# POWER_4.net
KiCad netlist of a schematic drawn in Altium Designer
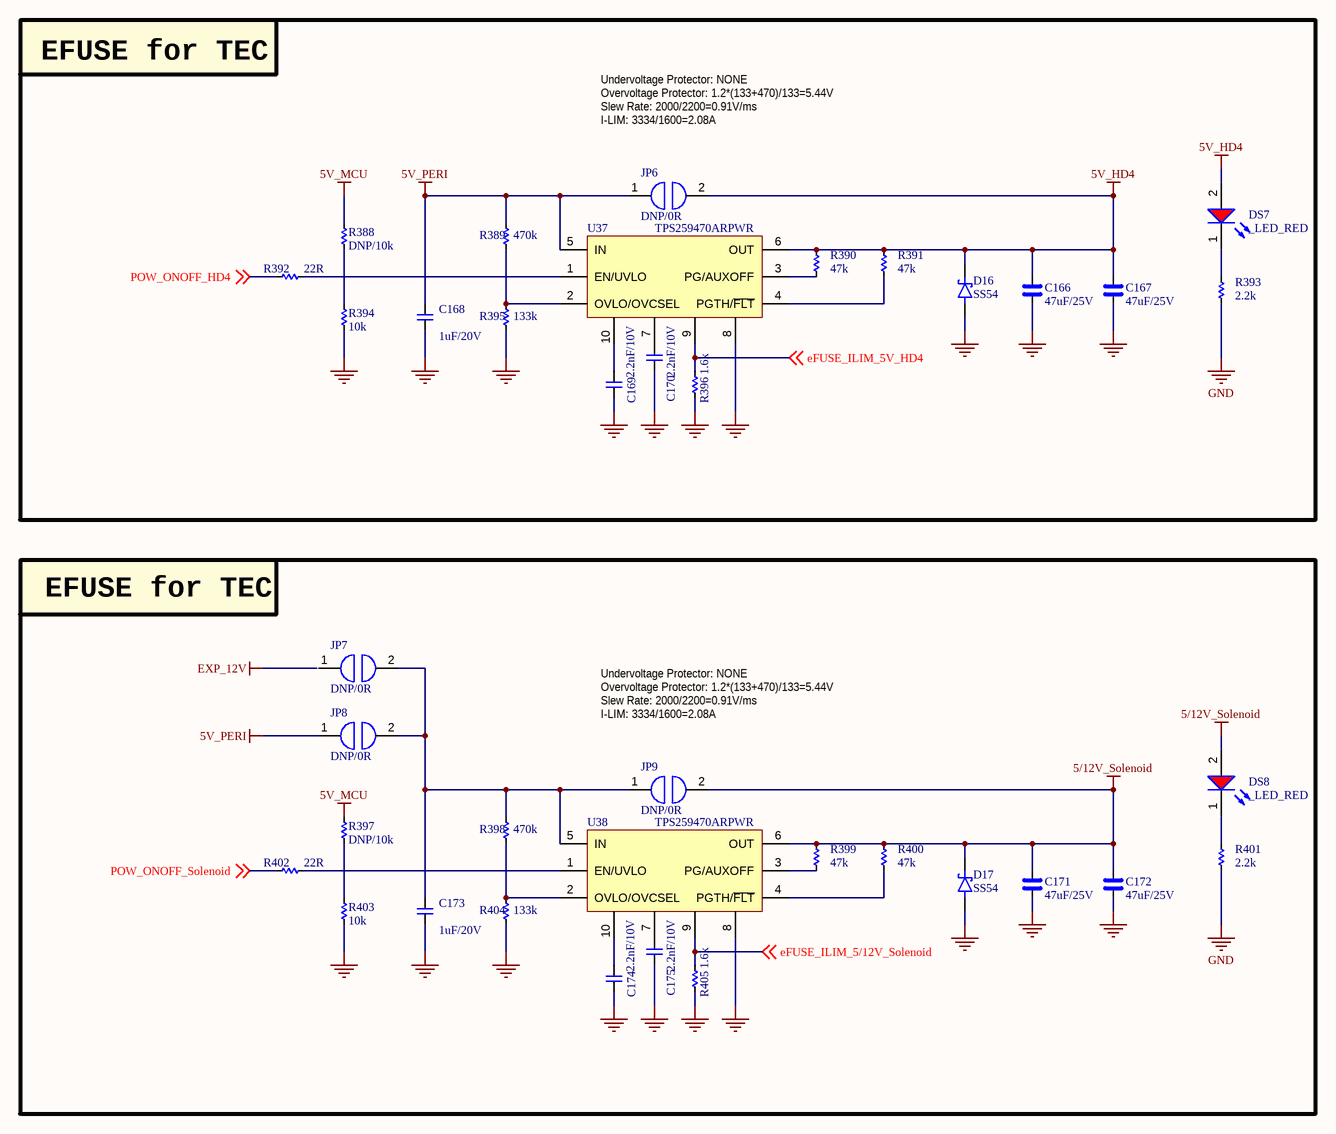
[diagram p0: POWER_4.SchDoc]

(export (version "E")
  (design (tool "Eeschema 10.0.6"))
  (components
    (comp (ref "C166")
      (value "47uF/25V")
      (footprint "CAP_C_3225X80")
      (description "CAP CHIP High Value")
      (libsource (lib "LABLIB") (part "_CAP_C_High_2"))
    )
    (comp (ref "C167")
      (value "47uF/25V")
      (footprint "CAP_C_3225X80")
      (description "CAP CHIP High Value")
      (libsource (lib "LABLIB") (part "_CAP_C_High_2"))
    )
    (comp (ref "C168")
      (value "1uF/20V")
      (footprint "CAP_C_1005X60")
      (description "CAP CHIP")
      (libsource (lib "LABLIB") (part "_CAP_C_2"))
    )
    (comp (ref "C169")
      (value "2.2nF/10V")
      (footprint "CAP_C_1005X60")
      (description "CAP CHIP")
      (libsource (lib "LABLIB") (part "_CAP_C_2"))
    )
    (comp (ref "C170")
      (value "2.2nF/10V")
      (footprint "CAP_C_1005X60")
      (description "CAP CHIP")
      (libsource (lib "LABLIB") (part "_CAP_C_2"))
    )
    (comp (ref "C171")
      (value "47uF/25V")
      (footprint "CAP_C_3225X80")
      (description "CAP CHIP High Value")
      (libsource (lib "LABLIB") (part "_CAP_C_High_2"))
    )
    (comp (ref "C172")
      (value "47uF/25V")
      (footprint "CAP_C_3225X80")
      (description "CAP CHIP High Value")
      (libsource (lib "LABLIB") (part "_CAP_C_High_2"))
    )
    (comp (ref "C173")
      (value "1uF/20V")
      (footprint "CAP_C_1005X60")
      (description "CAP CHIP")
      (libsource (lib "LABLIB") (part "_CAP_C_2"))
    )
    (comp (ref "C174")
      (value "2.2nF/10V")
      (footprint "CAP_C_1005X60")
      (description "CAP CHIP")
      (libsource (lib "LABLIB") (part "_CAP_C_2"))
    )
    (comp (ref "C175")
      (value "2.2nF/10V")
      (footprint "CAP_C_1005X60")
      (description "CAP CHIP")
      (libsource (lib "LABLIB") (part "_CAP_C_2"))
    )
    (comp (ref "D16")
      (value "SS54")
      (footprint "DO-214AC_SMA")
      (description "DIODE SCHOTTKY")
      (libsource (lib "LABLIB") (part "DIODE SCHOTTKY"))
    )
    (comp (ref "D17")
      (value "SS54")
      (footprint "DO-214AC_SMA")
      (description "DIODE SCHOTTKY")
      (libsource (lib "LABLIB") (part "DIODE SCHOTTKY"))
    )
    (comp (ref "DS7") (value "_LED_RED") (footprint "LED_0402") (libsource (lib "LABLIB") (part "_LED_RED")))
    (comp (ref "DS8") (value "_LED_RED") (footprint "LED_0402") (libsource (lib "LABLIB") (part "_LED_RED")))
    (comp (ref "JP6") (value "DNP/0R") (footprint "RES_C_1608X60") (libsource (lib "EXP_V1") (part "JUMPER")))
    (comp (ref "JP7") (value "DNP/0R") (footprint "RES_C_1608X60") (libsource (lib "EXP_V1") (part "JUMPER")))
    (comp (ref "JP8") (value "DNP/0R") (footprint "RES_C_1608X60") (libsource (lib "EXP_V1") (part "JUMPER")))
    (comp (ref "JP9") (value "DNP/0R") (footprint "RES_C_1608X60") (libsource (lib "EXP_V1") (part "JUMPER")))
    (comp (ref "R388")
      (value "DNP/10k")
      (footprint "RES_C_1005X40")
      (description "RES")
      (libsource (lib "LABLIB") (part "_RES_B_2"))
    )
    (comp (ref "R389")
      (value "470k")
      (footprint "RES_C_1005X40")
      (description "RES")
      (libsource (lib "LABLIB") (part "_RES_B_2"))
    )
    (comp (ref "R390")
      (value "47k")
      (footprint "RES_C_1005X40")
      (description "RES")
      (libsource (lib "LABLIB") (part "_RES_B_2"))
    )
    (comp (ref "R391")
      (value "47k")
      (footprint "RES_C_1005X40")
      (description "RES")
      (libsource (lib "LABLIB") (part "_RES_B_2"))
    )
    (comp (ref "R392")
      (value "22R")
      (footprint "RES_C_1005X40")
      (description "RES")
      (libsource (lib "LABLIB") (part "_RES_B_2"))
    )
    (comp (ref "R393")
      (value "2.2k")
      (footprint "RES_C_1005X40")
      (description "RES")
      (libsource (lib "LABLIB") (part "_RES_B_2"))
    )
    (comp (ref "R394")
      (value "10k")
      (footprint "RES_C_1005X40")
      (description "RES")
      (libsource (lib "LABLIB") (part "_RES_B_2"))
    )
    (comp (ref "R395")
      (value "133k")
      (footprint "RES_C_1005X40")
      (description "RES")
      (libsource (lib "LABLIB") (part "_RES_B_2"))
    )
    (comp (ref "R396")
      (value "1.6k")
      (footprint "RES_C_1005X40")
      (description "RES")
      (libsource (lib "LABLIB") (part "_RES_B_2"))
    )
    (comp (ref "R397")
      (value "DNP/10k")
      (footprint "RES_C_1005X40")
      (description "RES")
      (libsource (lib "LABLIB") (part "_RES_B_2"))
    )
    (comp (ref "R398")
      (value "470k")
      (footprint "RES_C_1005X40")
      (description "RES")
      (libsource (lib "LABLIB") (part "_RES_B_2"))
    )
    (comp (ref "R399")
      (value "47k")
      (footprint "RES_C_1005X40")
      (description "RES")
      (libsource (lib "LABLIB") (part "_RES_B_2"))
    )
    (comp (ref "R400")
      (value "47k")
      (footprint "RES_C_1005X40")
      (description "RES")
      (libsource (lib "LABLIB") (part "_RES_B_2"))
    )
    (comp (ref "R401")
      (value "2.2k")
      (footprint "RES_C_1005X40")
      (description "RES")
      (libsource (lib "LABLIB") (part "_RES_B_2"))
    )
    (comp (ref "R402")
      (value "22R")
      (footprint "RES_C_1005X40")
      (description "RES")
      (libsource (lib "LABLIB") (part "_RES_B_2"))
    )
    (comp (ref "R403")
      (value "10k")
      (footprint "RES_C_1005X40")
      (description "RES")
      (libsource (lib "LABLIB") (part "_RES_B_2"))
    )
    (comp (ref "R404")
      (value "133k")
      (footprint "RES_C_1005X40")
      (description "RES")
      (libsource (lib "LABLIB") (part "_RES_B_2"))
    )
    (comp (ref "R405")
      (value "1.6k")
      (footprint "RES_C_1005X40")
      (description "RES")
      (libsource (lib "LABLIB") (part "_RES_B_2"))
    )
    (comp (ref "U37")
      (value "TPS259470ARPWR")
      (footprint "VQFN-HR-10")
      (libsource (lib "EXP_HW_V3") (part "TPS259470ARPWR"))
    )
    (comp (ref "U38")
      (value "TPS259470ARPWR")
      (footprint "VQFN-HR-10")
      (libsource (lib "EXP_HW_V3") (part "TPS259470ARPWR"))
    )
  )
  (nets
    (net (code "1") (name "5V_HD4") (class "Default")
      (node (ref "C166") (pin "2") (pinfunction "2_2") (pintype "passive"))
      (node (ref "C167") (pin "2") (pinfunction "2_2") (pintype "passive"))
      (node (ref "D16") (pin "1") (pinfunction "K_1") (pintype "passive"))
      (node (ref "DS7") (pin "2") (pinfunction "A_2") (pintype "passive"))
      (node (ref "JP6") (pin "2") (pinfunction "2_2") (pintype "passive"))
      (node (ref "R390") (pin "2") (pinfunction "2_2") (pintype "passive"))
      (node (ref "R391") (pin "2") (pinfunction "2_2") (pintype "passive"))
      (node (ref "U37") (pin "6") (pinfunction "OUT_6") (pintype "passive"))
    )
    (net (code "2") (name "5V_MCU") (class "Default")
      (node (ref "R388") (pin "1") (pinfunction "1_1") (pintype "passive"))
      (node (ref "R397") (pin "1") (pinfunction "1_1") (pintype "passive"))
    )
    (net (code "3") (name "5V_PERI") (class "Default")
      (node (ref "C168") (pin "2") (pinfunction "2_2") (pintype "passive"))
      (node (ref "JP6") (pin "1") (pinfunction "1_1") (pintype "passive"))
      (node (ref "JP8") (pin "1") (pinfunction "1_1") (pintype "passive"))
      (node (ref "R389") (pin "2") (pinfunction "2_2") (pintype "passive"))
      (node (ref "U37") (pin "5") (pinfunction "IN_5") (pintype "passive"))
    )
    (net (code "4") (name "5{slash}12V_Solenoid") (class "Default")
      (node (ref "C171") (pin "2") (pinfunction "2_2") (pintype "passive"))
      (node (ref "C172") (pin "2") (pinfunction "2_2") (pintype "passive"))
      (node (ref "D17") (pin "1") (pinfunction "K_1") (pintype "passive"))
      (node (ref "DS8") (pin "2") (pinfunction "A_2") (pintype "passive"))
      (node (ref "JP9") (pin "2") (pinfunction "2_2") (pintype "passive"))
      (node (ref "R399") (pin "2") (pinfunction "2_2") (pintype "passive"))
      (node (ref "R400") (pin "2") (pinfunction "2_2") (pintype "passive"))
      (node (ref "U38") (pin "6") (pinfunction "OUT_6") (pintype "passive"))
    )
    (net (code "6") (name "GND") (class "Default")
      (node (ref "C166") (pin "1") (pinfunction "1_1") (pintype "passive"))
      (node (ref "C167") (pin "1") (pinfunction "1_1") (pintype "passive"))
      (node (ref "C168") (pin "1") (pinfunction "1_1") (pintype "passive"))
      (node (ref "C169") (pin "1") (pinfunction "1_1") (pintype "passive"))
      (node (ref "C170") (pin "1") (pinfunction "1_1") (pintype "passive"))
      (node (ref "C171") (pin "1") (pinfunction "1_1") (pintype "passive"))
      (node (ref "C172") (pin "1") (pinfunction "1_1") (pintype "passive"))
      (node (ref "C173") (pin "1") (pinfunction "1_1") (pintype "passive"))
      (node (ref "C174") (pin "1") (pinfunction "1_1") (pintype "passive"))
      (node (ref "C175") (pin "1") (pinfunction "1_1") (pintype "passive"))
      (node (ref "D16") (pin "2") (pinfunction "A_2") (pintype "passive"))
      (node (ref "D17") (pin "2") (pinfunction "A_2") (pintype "passive"))
      (node (ref "R393") (pin "1") (pinfunction "1_1") (pintype "passive"))
      (node (ref "R394") (pin "2") (pinfunction "2_2") (pintype "passive"))
      (node (ref "R395") (pin "1") (pinfunction "1_1") (pintype "passive"))
      (node (ref "R396") (pin "1") (pinfunction "1_1") (pintype "passive"))
      (node (ref "R401") (pin "1") (pinfunction "1_1") (pintype "passive"))
      (node (ref "R403") (pin "2") (pinfunction "2_2") (pintype "passive"))
      (node (ref "R404") (pin "1") (pinfunction "1_1") (pintype "passive"))
      (node (ref "R405") (pin "1") (pinfunction "1_1") (pintype "passive"))
      (node (ref "U37") (pin "8") (pinfunction "8_8") (pintype "passive"))
      (node (ref "U38") (pin "8") (pinfunction "8_8") (pintype "passive"))
    )
    (net (code "7") (name "Net-(C169-Pad2)") (class "Default")
      (node (ref "C169") (pin "2") (pinfunction "2_2") (pintype "passive"))
      (node (ref "U37") (pin "10") (pinfunction "10_10") (pintype "passive"))
    )
    (net (code "8") (name "Net-(C170-Pad2)") (class "Default")
      (node (ref "C170") (pin "2") (pinfunction "2_2") (pintype "passive"))
      (node (ref "U37") (pin "7") (pinfunction "7_7") (pintype "passive"))
    )
    (net (code "9") (name "Net-(C174-Pad2)") (class "Default")
      (node (ref "C174") (pin "2") (pinfunction "2_2") (pintype "passive"))
      (node (ref "U38") (pin "10") (pinfunction "10_10") (pintype "passive"))
    )
    (net (code "10") (name "Net-(C175-Pad2)") (class "Default")
      (node (ref "C175") (pin "2") (pinfunction "2_2") (pintype "passive"))
      (node (ref "U38") (pin "7") (pinfunction "7_7") (pintype "passive"))
    )
    (net (code "11") (name "Net-(DS7-K)") (class "Default")
      (node (ref "DS7") (pin "1") (pinfunction "K_1") (pintype "passive"))
      (node (ref "R393") (pin "2") (pinfunction "2_2") (pintype "passive"))
    )
    (net (code "12") (name "Net-(DS8-K)") (class "Default")
      (node (ref "DS8") (pin "1") (pinfunction "K_1") (pintype "passive"))
      (node (ref "R401") (pin "2") (pinfunction "2_2") (pintype "passive"))
    )
    (net (code "13") (name "Net-(R388-Pad2)") (class "Default")
      (node (ref "R388") (pin "2") (pinfunction "2_2") (pintype "passive"))
      (node (ref "R394") (pin "1") (pinfunction "1_1") (pintype "passive"))
    )
    (net (code "14") (name "Net-(R397-Pad2)") (class "Default")
      (node (ref "R397") (pin "2") (pinfunction "2_2") (pintype "passive"))
      (node (ref "R403") (pin "1") (pinfunction "1_1") (pintype "passive"))
    )
    (net (code "15") (name "Net-(U37-EN{slash}UVLO)") (class "Default")
      (node (ref "R392") (pin "1") (pinfunction "1_1") (pintype "passive"))
      (node (ref "U37") (pin "1") (pinfunction "EN/UVLO_1") (pintype "passive"))
    )
    (net (code "16") (name "Net-(U37-OVLO{slash}OVCSEL)") (class "Default")
      (node (ref "R389") (pin "1") (pinfunction "1_1") (pintype "passive"))
      (node (ref "R395") (pin "2") (pinfunction "2_2") (pintype "passive"))
      (node (ref "U37") (pin "2") (pinfunction "OVLO/OVCSEL_2") (pintype "passive"))
    )
    (net (code "17") (name "Net-(U37-PGTH{slash}~{FLT})") (class "Default")
      (node (ref "R391") (pin "1") (pinfunction "1_1") (pintype "passive"))
      (node (ref "U37") (pin "4") (pinfunction "PGTH/~{FLT}_4") (pintype "passive"))
    )
    (net (code "18") (name "Net-(U37-PG{slash}AUXOFF)") (class "Default")
      (node (ref "R390") (pin "1") (pinfunction "1_1") (pintype "passive"))
      (node (ref "U37") (pin "3") (pinfunction "PG/AUXOFF_3") (pintype "passive"))
    )
    (net (code "19") (name "Net-(U38-EN{slash}UVLO)") (class "Default")
      (node (ref "R402") (pin "1") (pinfunction "1_1") (pintype "passive"))
      (node (ref "U38") (pin "1") (pinfunction "EN/UVLO_1") (pintype "passive"))
    )
    (net (code "20") (name "Net-(U38-IN)") (class "Default")
      (node (ref "C173") (pin "2") (pinfunction "2_2") (pintype "passive"))
      (node (ref "JP7") (pin "2") (pinfunction "2_2") (pintype "passive"))
      (node (ref "JP8") (pin "2") (pinfunction "2_2") (pintype "passive"))
      (node (ref "JP9") (pin "1") (pinfunction "1_1") (pintype "passive"))
      (node (ref "R398") (pin "2") (pinfunction "2_2") (pintype "passive"))
      (node (ref "U38") (pin "5") (pinfunction "IN_5") (pintype "passive"))
    )
    (net (code "21") (name "Net-(U38-OVLO{slash}OVCSEL)") (class "Default")
      (node (ref "R398") (pin "1") (pinfunction "1_1") (pintype "passive"))
      (node (ref "R404") (pin "2") (pinfunction "2_2") (pintype "passive"))
      (node (ref "U38") (pin "2") (pinfunction "OVLO/OVCSEL_2") (pintype "passive"))
    )
    (net (code "22") (name "Net-(U38-PGTH{slash}~{FLT})") (class "Default")
      (node (ref "R400") (pin "1") (pinfunction "1_1") (pintype "passive"))
      (node (ref "U38") (pin "4") (pinfunction "PGTH/~{FLT}_4") (pintype "passive"))
    )
    (net (code "23") (name "Net-(U38-PG{slash}AUXOFF)") (class "Default")
      (node (ref "R399") (pin "1") (pinfunction "1_1") (pintype "passive"))
      (node (ref "U38") (pin "3") (pinfunction "PG/AUXOFF_3") (pintype "passive"))
    )
    (net (code "24") (name "POW_ONOFF_HD4") (class "Default")
      (node (ref "R392") (pin "2") (pinfunction "2_2") (pintype "passive"))
    )
    (net (code "25") (name "POW_ONOFF_Solenoid") (class "Default")
      (node (ref "R402") (pin "2") (pinfunction "2_2") (pintype "passive"))
    )
    (net (code "26") (name "eFUSE_ILIM_5V_HD4") (class "Default")
      (node (ref "R396") (pin "2") (pinfunction "2_2") (pintype "passive"))
      (node (ref "U37") (pin "9") (pinfunction "9_9") (pintype "passive"))
    )
    (net (code "27") (name "eFUSE_ILIM_5{slash}12V_Solenoid") (class "Default")
      (node (ref "R405") (pin "2") (pinfunction "2_2") (pintype "passive"))
      (node (ref "U38") (pin "9") (pinfunction "9_9") (pintype "passive"))
    )
    (net (code "28") (name "unconnected-(JP7-Pad1)") (class "Default")
      (node (ref "JP7") (pin "1") (pinfunction "1_1") (pintype "passive"))
    )
  )
)
